# hothouse-io-no-branding.net
KiCad netlist of a schematic drawn in EAGLE
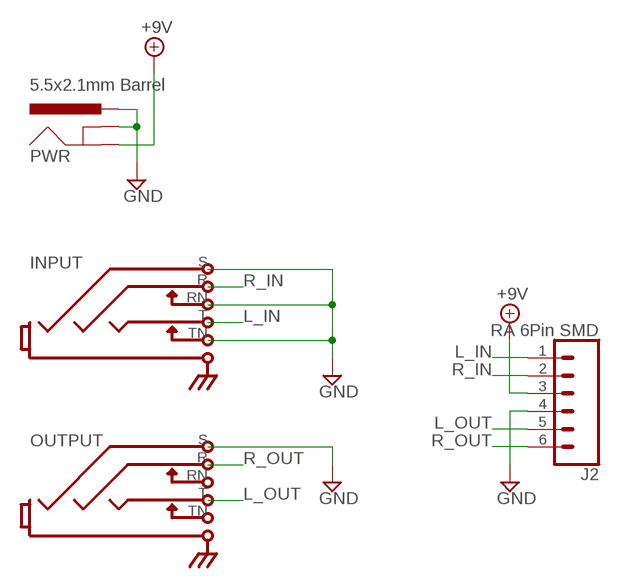
[diagram p0: schematic, sheet 1]

(export (version "E")
  (design (tool "Eeschema 10.0.6"))
  (components
    (comp (ref "INPUT")
      (value "STEREOSW2GND")
      (footprint "eagle-import:NEUTRIK-NRJ6HM-1")
      (libsource (lib "eagle-import") (part "STEREOSW2GND"))
    )
    (comp (ref "J2")
      (value "RA 6Pin SMD")
      (footprint "eagle-import:1X06")
      (libsource (lib "eagle-import") (part "CONN_06SILK_FEMALE_PTH"))
    )
    (comp (ref "OUTPUT")
      (value "STEREOSW2GND")
      (footprint "eagle-import:NEUTRIK-NRJ6HM-1")
      (libsource (lib "eagle-import") (part "STEREOSW2GND"))
    )
    (comp (ref "PWR")
      (value "5.5x2.1mm Barrel")
      (footprint "eagle-import:POWER_JACK_PTH_SLOT")
      (libsource (lib "eagle-import") (part "POWER_JACKPOWER_JACK_SLOT"))
    )
  )
  (nets
    (net (code "1") (name "+9V") (class "Default")
      (node (ref "J2") (pin "3") (pinfunction "3_3") (pintype "passive"))
      (node (ref "PWR") (pin "GND") (pinfunction "GND_GND") (pintype "bidirectional"))
    )
    (net (code "2") (name "/L_IN") (class "Default")
      (node (ref "INPUT") (pin "T") (pinfunction "T_T") (pintype "passive"))
      (node (ref "J2") (pin "1") (pinfunction "1_1") (pintype "passive"))
    )
    (net (code "3") (name "/L_OUT") (class "Default")
      (node (ref "J2") (pin "5") (pinfunction "5_5") (pintype "passive"))
      (node (ref "OUTPUT") (pin "T") (pinfunction "T_T") (pintype "passive"))
    )
    (net (code "4") (name "/R_IN") (class "Default")
      (node (ref "INPUT") (pin "R") (pinfunction "R_R") (pintype "passive"))
      (node (ref "J2") (pin "2") (pinfunction "2_2") (pintype "passive"))
    )
    (net (code "5") (name "/R_OUT") (class "Default")
      (node (ref "J2") (pin "6") (pinfunction "6_6") (pintype "passive"))
      (node (ref "OUTPUT") (pin "R") (pinfunction "R_R") (pintype "passive"))
    )
    (net (code "6") (name "GND") (class "Default")
      (node (ref "INPUT") (pin "RN") (pinfunction "RN_RN") (pintype "passive"))
      (node (ref "INPUT") (pin "S") (pinfunction "S_S") (pintype "passive"))
      (node (ref "INPUT") (pin "TN") (pinfunction "TN_TN") (pintype "passive"))
      (node (ref "J2") (pin "4") (pinfunction "4_4") (pintype "passive"))
      (node (ref "OUTPUT") (pin "S") (pinfunction "S_S") (pintype "passive"))
      (node (ref "PWR") (pin "GNDBREAK") (pinfunction "GNDBREAK_GNDBREAK") (pintype "bidirectional"))
      (node (ref "PWR") (pin "PWR") (pinfunction "PWR_PWR") (pintype "bidirectional"))
    )
    (net (code "7") (name "unconnected-(OUTPUT-PadRN)") (class "Default")
      (node (ref "OUTPUT") (pin "RN") (pinfunction "RN_RN") (pintype "passive"))
    )
    (net (code "8") (name "unconnected-(OUTPUT-PadTN)") (class "Default")
      (node (ref "OUTPUT") (pin "TN") (pinfunction "TN_TN") (pintype "passive"))
    )
  )
)
